# TeamH-PDS.net
KiCad netlist of a schematic drawn in EAGLE
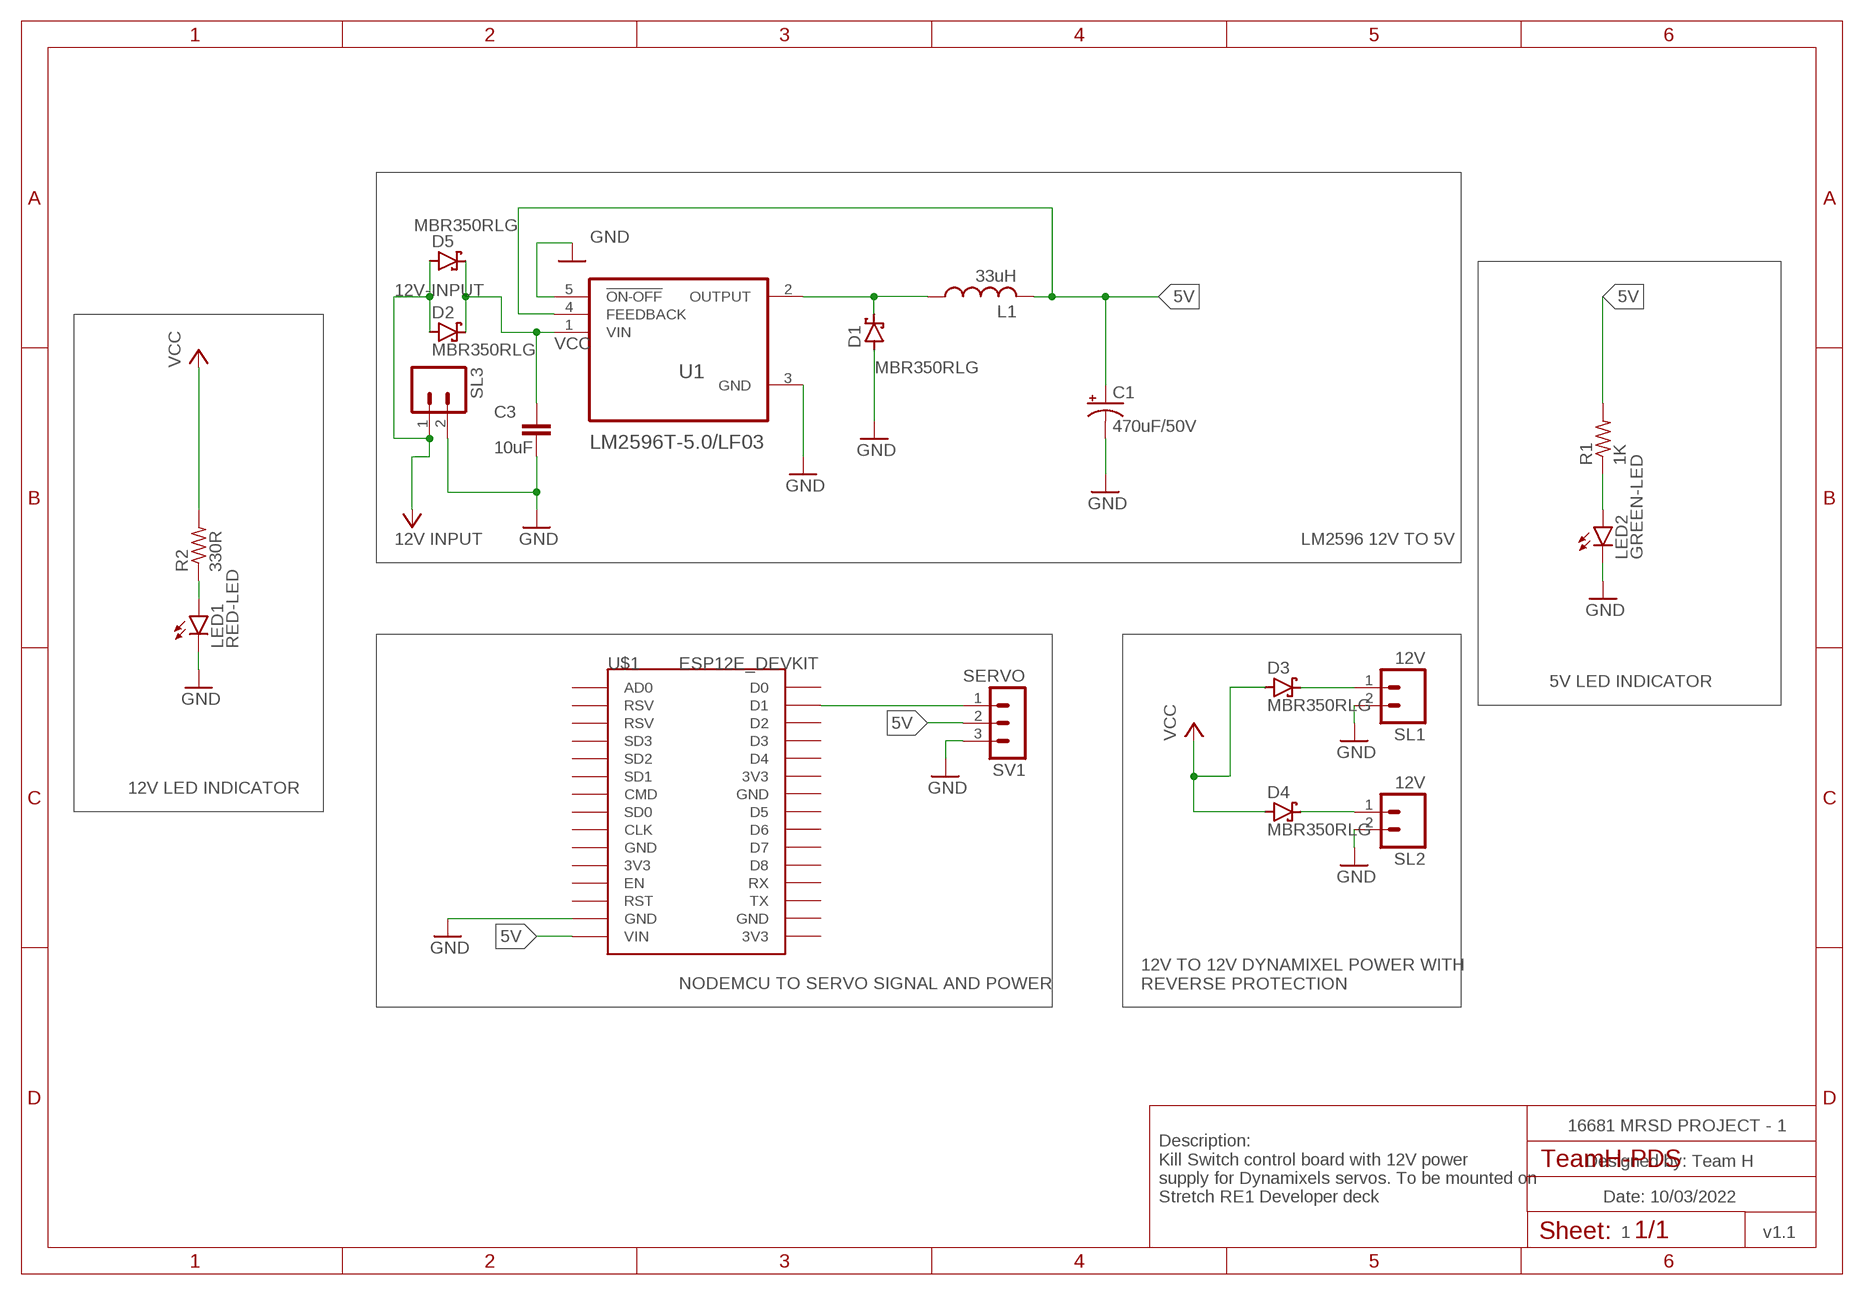
[diagram p0: schematic, sheet 1]

(export (version "E")
  (design (tool "Eeschema 10.0.6"))
  (components
    (comp (ref "C1")
      (value "470uF/50V")
      (footprint "eagle-import:E2-5")
      (libsource (lib "eagle-import") (part "CPOL-USE2-5"))
    )
    (comp (ref "C3")
      (value "10uF")
      (footprint "eagle-import:C2.5-3")
      (libsource (lib "eagle-import") (part "C2,5-3"))
    )
    (comp (ref "D1")
      (value "MBR350RLG")
      (footprint "eagle-import:C4111-15")
      (libsource (lib "eagle-import") (part "1N5908"))
    )
    (comp (ref "D2")
      (value "MBR350RLG")
      (footprint "eagle-import:C4111-15")
      (libsource (lib "eagle-import") (part "1N5908"))
    )
    (comp (ref "D3")
      (value "MBR350RLG")
      (footprint "eagle-import:C4111-15")
      (libsource (lib "eagle-import") (part "1N5908"))
    )
    (comp (ref "D4")
      (value "MBR350RLG")
      (footprint "eagle-import:C4111-15")
      (libsource (lib "eagle-import") (part "1N5908"))
    )
    (comp (ref "D5")
      (value "MBR350RLG")
      (footprint "eagle-import:C4111-15")
      (libsource (lib "eagle-import") (part "1N5908"))
    )
    (comp (ref "L1")
      (value "33uH")
      (footprint "eagle-import:0207_7")
      (libsource (lib "eagle-import") (part "L-US0207/7"))
    )
    (comp (ref "LED1")
      (value "RED-LED")
      (footprint "eagle-import:LED5MM")
      (libsource (lib "eagle-import") (part "LED5MM"))
    )
    (comp (ref "LED2")
      (value "GREEN-LED")
      (footprint "eagle-import:LED5MM")
      (libsource (lib "eagle-import") (part "LED5MM"))
    )
    (comp (ref "R1")
      (value "1K")
      (footprint "eagle-import:0204_5")
      (libsource (lib "eagle-import") (part "R-US_0204/5"))
    )
    (comp (ref "R2")
      (value "330R")
      (footprint "eagle-import:0204_5")
      (libsource (lib "eagle-import") (part "R-US_0204/5"))
    )
    (comp (ref "SL1")
      (value "12V")
      (footprint "eagle-import:02P")
      (libsource (lib "eagle-import") (part "M02"))
    )
    (comp (ref "SL2")
      (value "12V")
      (footprint "eagle-import:02P")
      (libsource (lib "eagle-import") (part "M02"))
    )
    (comp (ref "SL3")
      (value "12V-INPUT")
      (footprint "eagle-import:02P")
      (libsource (lib "eagle-import") (part "M02"))
    )
    (comp (ref "SV1")
      (value "SERVO")
      (footprint "eagle-import:MA03-1")
      (libsource (lib "eagle-import") (part "MA03-1"))
    )
    (comp (ref "U$1")
      (value "ESP12E_DEVKIT")
      (footprint "eagle-import:ESP12E_DEVKIT")
      (libsource (lib "eagle-import") (part "ESP12E_DEVKIT"))
    )
    (comp (ref "U1")
      (value "LM2596T-5.0/LF03")
      (footprint "eagle-import:TO170P1016X470X2092-5")
      (fields (field (name "MF") "Texas Instruments"))
      (libsource (lib "eagle-import") (part "LM2596T-5.0/LF03"))
    )
  )
  (nets
    (net (code "1") (name "5V") (class "Default")
      (node (ref "C1") (pin "+") (pinfunction "+_+") (pintype "passive"))
      (node (ref "L1") (pin "2") (pinfunction "2_2") (pintype "passive"))
      (node (ref "R1") (pin "2") (pinfunction "2_2") (pintype "passive"))
      (node (ref "SV1") (pin "2") (pinfunction "2_2") (pintype "passive"))
      (node (ref "U$1") (pin "VIN") (pinfunction "VIN_VIN") (pintype "bidirectional"))
      (node (ref "U1") (pin "4") (pinfunction "FEEDBACK_4") (pintype "input"))
    )
    (net (code "2") (name "GND") (class "Default")
      (node (ref "C1") (pin "-") (pinfunction "-_-") (pintype "passive"))
      (node (ref "C3") (pin "2") (pinfunction "2_2") (pintype "passive"))
      (node (ref "D1") (pin "A") (pinfunction "A_A") (pintype "passive"))
      (node (ref "LED1") (pin "K") (pinfunction "C_K") (pintype "passive"))
      (node (ref "LED2") (pin "K") (pinfunction "C_K") (pintype "passive"))
      (node (ref "SL1") (pin "2") (pinfunction "2_2") (pintype "passive"))
      (node (ref "SL2") (pin "2") (pinfunction "2_2") (pintype "passive"))
      (node (ref "SL3") (pin "2") (pinfunction "2_2") (pintype "passive"))
      (node (ref "SV1") (pin "3") (pinfunction "3_3") (pintype "passive"))
      (node (ref "U$1") (pin "GND@1") (pinfunction "GND_GND@1") (pintype "bidirectional"))
      (node (ref "U1") (pin "3") (pinfunction "GND_3") (pintype "power_in"))
      (node (ref "U1") (pin "5") (pinfunction "~{ON-OFF}_5") (pintype "input"))
    )
    (net (code "3") (name "Net-(D3-PadC)") (class "Default")
      (node (ref "D3") (pin "C") (pinfunction "C_C") (pintype "passive"))
      (node (ref "SL1") (pin "1") (pinfunction "1_1") (pintype "passive"))
    )
    (net (code "4") (name "Net-(D4-PadC)") (class "Default")
      (node (ref "D4") (pin "C") (pinfunction "C_C") (pintype "passive"))
      (node (ref "SL2") (pin "1") (pinfunction "1_1") (pintype "passive"))
    )
    (net (code "5") (name "Net-(LED1-PadA)") (class "Default")
      (node (ref "LED1") (pin "A") (pinfunction "A_A") (pintype "passive"))
      (node (ref "R2") (pin "1") (pinfunction "1_1") (pintype "passive"))
    )
    (net (code "6") (name "Net-(LED2-PadA)") (class "Default")
      (node (ref "LED2") (pin "A") (pinfunction "A_A") (pintype "passive"))
      (node (ref "R1") (pin "1") (pinfunction "1_1") (pintype "passive"))
    )
    (net (code "7") (name "Net-(SV1-Pad1)") (class "Default")
      (node (ref "SV1") (pin "1") (pinfunction "1_1") (pintype "passive"))
      (node (ref "U$1") (pin "D1") (pinfunction "D1_D1") (pintype "bidirectional"))
    )
    (net (code "8") (name "Net-(U1-OUTPUT)") (class "Default")
      (node (ref "D1") (pin "C") (pinfunction "C_C") (pintype "passive"))
      (node (ref "L1") (pin "1") (pinfunction "1_1") (pintype "passive"))
      (node (ref "U1") (pin "2") (pinfunction "OUTPUT_2") (pintype "output"))
    )
    (net (code "9") (name "Net-(U1-VIN)") (class "Default")
      (node (ref "C3") (pin "1") (pinfunction "1_1") (pintype "passive"))
      (node (ref "D2") (pin "C") (pinfunction "C_C") (pintype "passive"))
      (node (ref "D5") (pin "C") (pinfunction "C_C") (pintype "passive"))
      (node (ref "U1") (pin "1") (pinfunction "VIN_1") (pintype "input"))
    )
    (net (code "10") (name "VCC") (class "Default")
      (node (ref "D2") (pin "A") (pinfunction "A_A") (pintype "passive"))
      (node (ref "D3") (pin "A") (pinfunction "A_A") (pintype "passive"))
      (node (ref "D4") (pin "A") (pinfunction "A_A") (pintype "passive"))
      (node (ref "D5") (pin "A") (pinfunction "A_A") (pintype "passive"))
      (node (ref "R2") (pin "2") (pinfunction "2_2") (pintype "passive"))
      (node (ref "SL3") (pin "1") (pinfunction "1_1") (pintype "passive"))
    )
    (net (code "11") (name "unconnected-(U$1-3V3-Pad3V3@0)") (class "Default")
      (node (ref "U$1") (pin "3V3@0") (pinfunction "3V3_3V3@0") (pintype "bidirectional"))
    )
    (net (code "12") (name "unconnected-(U$1-3V3-Pad3V3@1)") (class "Default")
      (node (ref "U$1") (pin "3V3@1") (pinfunction "3V3_3V3@1") (pintype "bidirectional"))
    )
    (net (code "13") (name "unconnected-(U$1-3V3-Pad3V3@2)") (class "Default")
      (node (ref "U$1") (pin "3V3@2") (pinfunction "3V3_3V3@2") (pintype "bidirectional"))
    )
    (net (code "14") (name "unconnected-(U$1-GND-PadGND@0)") (class "Default")
      (node (ref "U$1") (pin "GND@0") (pinfunction "GND_GND@0") (pintype "bidirectional"))
    )
    (net (code "15") (name "unconnected-(U$1-GND-PadGND@2)") (class "Default")
      (node (ref "U$1") (pin "GND@2") (pinfunction "GND_GND@2") (pintype "bidirectional"))
    )
    (net (code "16") (name "unconnected-(U$1-GND-PadGND@3)") (class "Default")
      (node (ref "U$1") (pin "GND@3") (pinfunction "GND_GND@3") (pintype "bidirectional"))
    )
    (net (code "17") (name "unconnected-(U$1-PadAD0)") (class "Default")
      (node (ref "U$1") (pin "AD0") (pinfunction "AD0_AD0") (pintype "bidirectional"))
    )
    (net (code "18") (name "unconnected-(U$1-PadCLK)") (class "Default")
      (node (ref "U$1") (pin "CLK") (pinfunction "CLK_CLK") (pintype "bidirectional"))
    )
    (net (code "19") (name "unconnected-(U$1-PadCMD)") (class "Default")
      (node (ref "U$1") (pin "CMD") (pinfunction "CMD_CMD") (pintype "bidirectional"))
    )
    (net (code "20") (name "unconnected-(U$1-PadD0)") (class "Default")
      (node (ref "U$1") (pin "D0") (pinfunction "D0_D0") (pintype "bidirectional"))
    )
    (net (code "21") (name "unconnected-(U$1-PadD2)") (class "Default")
      (node (ref "U$1") (pin "D2") (pinfunction "D2_D2") (pintype "bidirectional"))
    )
    (net (code "22") (name "unconnected-(U$1-PadD3)") (class "Default")
      (node (ref "U$1") (pin "D3") (pinfunction "D3_D3") (pintype "bidirectional"))
    )
    (net (code "23") (name "unconnected-(U$1-PadD4)") (class "Default")
      (node (ref "U$1") (pin "D4") (pinfunction "D4_D4") (pintype "bidirectional"))
    )
    (net (code "24") (name "unconnected-(U$1-PadD5)") (class "Default")
      (node (ref "U$1") (pin "D5") (pinfunction "D5_D5") (pintype "bidirectional"))
    )
    (net (code "25") (name "unconnected-(U$1-PadD6)") (class "Default")
      (node (ref "U$1") (pin "D6") (pinfunction "D6_D6") (pintype "bidirectional"))
    )
    (net (code "26") (name "unconnected-(U$1-PadD7)") (class "Default")
      (node (ref "U$1") (pin "D7") (pinfunction "D7_D7") (pintype "bidirectional"))
    )
    (net (code "27") (name "unconnected-(U$1-PadD8)") (class "Default")
      (node (ref "U$1") (pin "D8") (pinfunction "D8_D8") (pintype "bidirectional"))
    )
    (net (code "28") (name "unconnected-(U$1-PadEN)") (class "Default")
      (node (ref "U$1") (pin "EN") (pinfunction "EN_EN") (pintype "bidirectional"))
    )
    (net (code "29") (name "unconnected-(U$1-PadRST)") (class "Default")
      (node (ref "U$1") (pin "RST") (pinfunction "RST_RST") (pintype "bidirectional"))
    )
    (net (code "30") (name "unconnected-(U$1-PadRX)") (class "Default")
      (node (ref "U$1") (pin "RX") (pinfunction "RX_RX") (pintype "bidirectional"))
    )
    (net (code "31") (name "unconnected-(U$1-PadSD0)") (class "Default")
      (node (ref "U$1") (pin "SD0") (pinfunction "SD0_SD0") (pintype "bidirectional"))
    )
    (net (code "32") (name "unconnected-(U$1-PadSD1)") (class "Default")
      (node (ref "U$1") (pin "SD1") (pinfunction "SD1_SD1") (pintype "bidirectional"))
    )
    (net (code "33") (name "unconnected-(U$1-PadSD2)") (class "Default")
      (node (ref "U$1") (pin "SD2") (pinfunction "SD2_SD2") (pintype "bidirectional"))
    )
    (net (code "34") (name "unconnected-(U$1-PadSD3)") (class "Default")
      (node (ref "U$1") (pin "SD3") (pinfunction "SD3_SD3") (pintype "bidirectional"))
    )
    (net (code "35") (name "unconnected-(U$1-PadTX)") (class "Default")
      (node (ref "U$1") (pin "TX") (pinfunction "TX_TX") (pintype "bidirectional"))
    )
    (net (code "36") (name "unconnected-(U$1-RSV-PadRSV@0)") (class "Default")
      (node (ref "U$1") (pin "RSV@0") (pinfunction "RSV_RSV@0") (pintype "bidirectional"))
    )
    (net (code "37") (name "unconnected-(U$1-RSV-PadRSV@1)") (class "Default")
      (node (ref "U$1") (pin "RSV@1") (pinfunction "RSV_RSV@1") (pintype "bidirectional"))
    )
  )
)
